# Boost.net
KiCad netlist of a schematic drawn in EAGLE
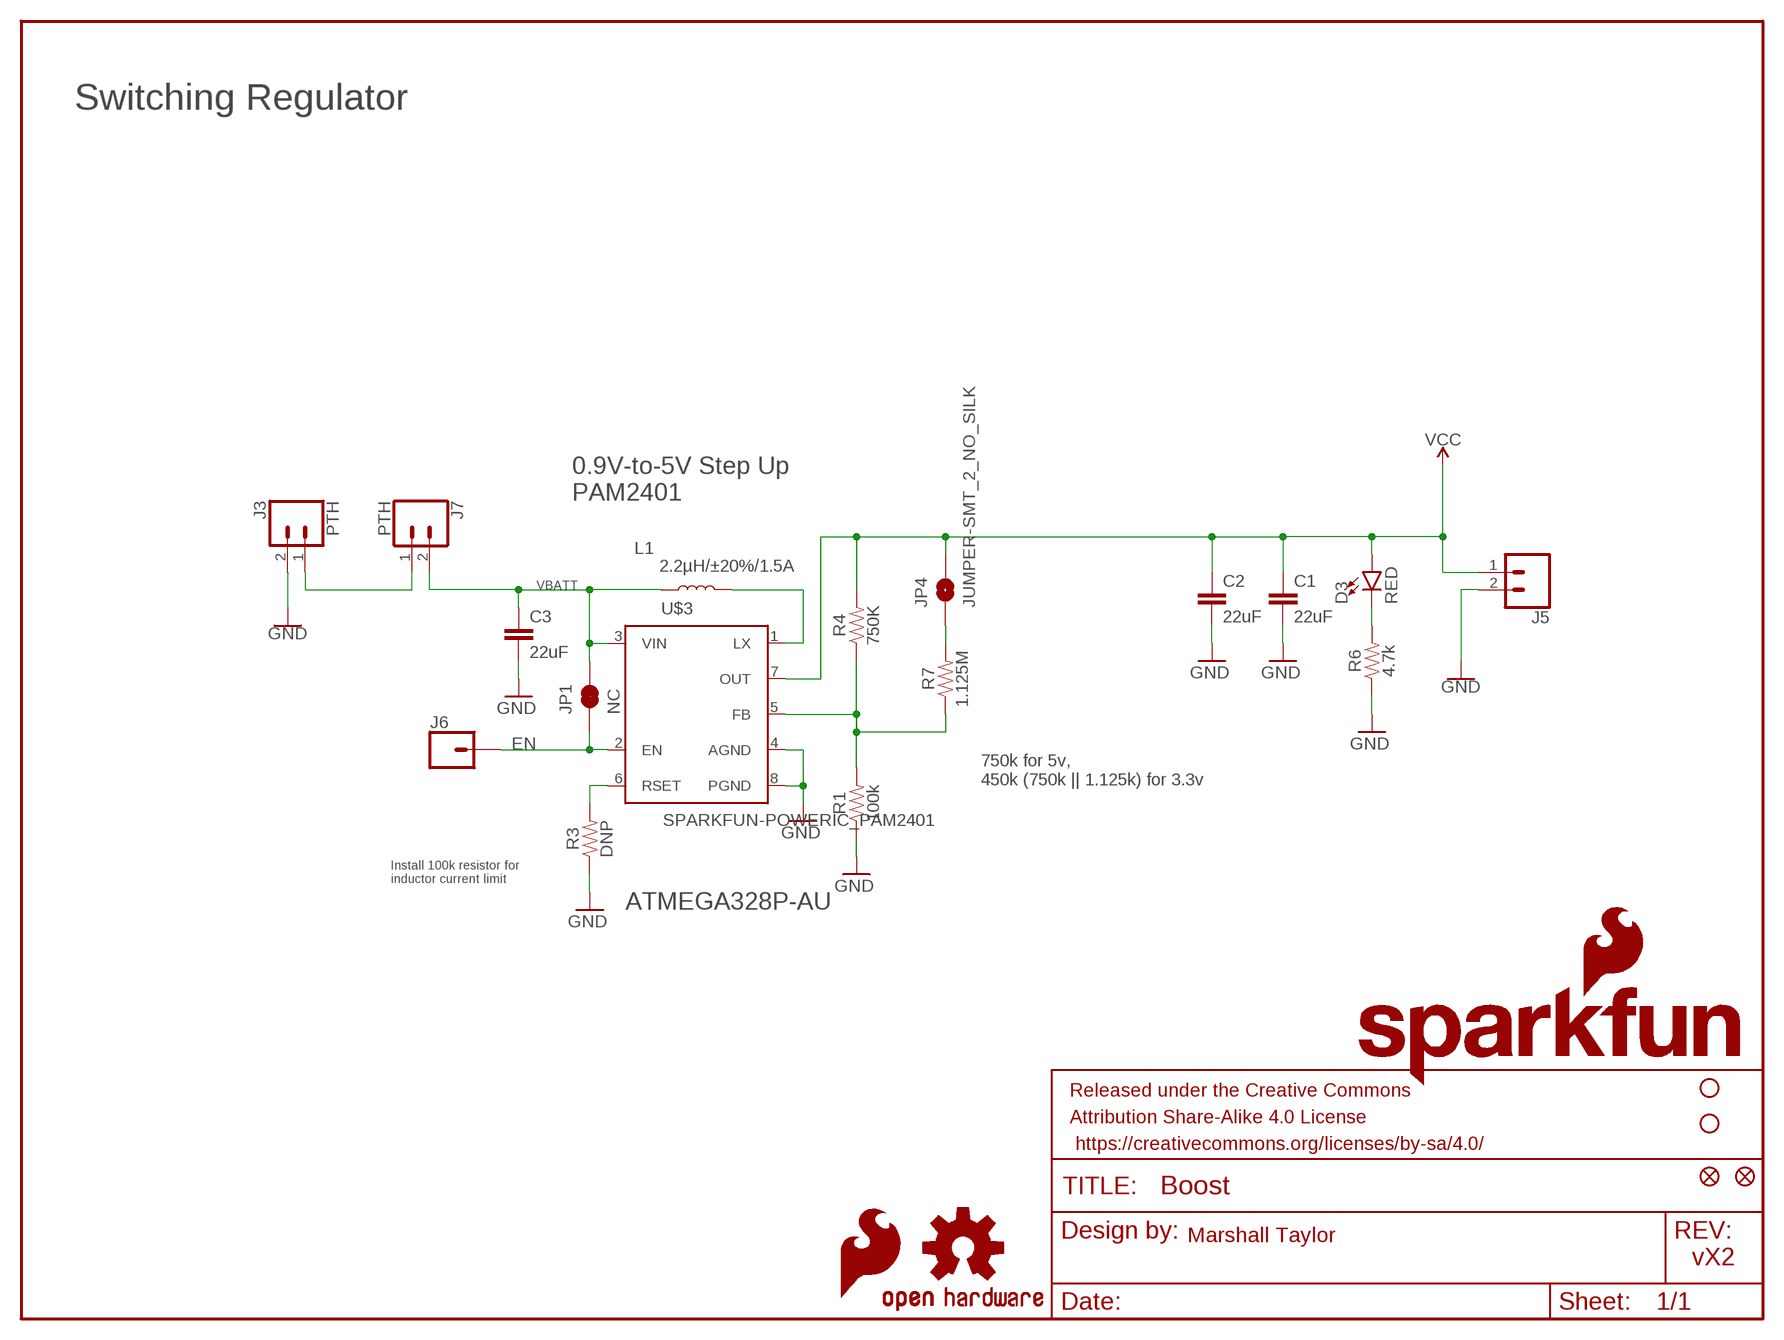
[diagram p0: schematic, sheet 1]

(export (version "E")
  (design (tool "Eeschema 10.0.6"))
  (components
    (comp (ref "C1")
      (value "22uF")
      (footprint "eagle-import:0805")
      (libsource (lib "eagle-import") (part "22UF-0805-6.3V-20%"))
    )
    (comp (ref "C2")
      (value "22uF")
      (footprint "eagle-import:0805")
      (libsource (lib "eagle-import") (part "22UF-0805-6.3V-20%"))
    )
    (comp (ref "C3")
      (value "22uF")
      (footprint "eagle-import:0805")
      (libsource (lib "eagle-import") (part "22UF-0805-6.3V-20%"))
    )
    (comp (ref "D3")
      (value "RED")
      (footprint "eagle-import:LED-0603")
      (libsource (lib "eagle-import") (part "LED-RED0603"))
    )
    (comp (ref "FRAME1")
      (value "FRAME-LETTER")
      (footprint "eagle-import:CREATIVE_COMMONS")
      (libsource (lib "eagle-import") (part "FRAME-LETTER"))
    )
    (comp (ref "J3")
      (value "PTH")
      (footprint "eagle-import:1X02_NO_SILK")
      (libsource (lib "eagle-import") (part "CONN_021X02_NO_SILK"))
    )
    (comp (ref "J5")
      (value "CONN_021X02_NO_SILK")
      (footprint "eagle-import:1X02_NO_SILK")
      (libsource (lib "eagle-import") (part "CONN_021X02_NO_SILK"))
    )
    (comp (ref "J6")
      (value "CONN_01")
      (footprint "eagle-import:1X01")
      (libsource (lib "eagle-import") (part "CONN_01"))
    )
    (comp (ref "J7")
      (value "PTH")
      (footprint "eagle-import:1X02_NO_SILK")
      (libsource (lib "eagle-import") (part "CONN_021X02_NO_SILK"))
    )
    (comp (ref "JP1")
      (value "NC")
      (footprint "eagle-import:SMT-JUMPER_2_NC_TRACE_NO-SILK")
      (libsource (lib "eagle-import") (part "JUMPER-SMT_2_NC_TRACE_NO-SILK"))
    )
    (comp (ref "JP2")
      (value "FIDUCIAL1X2")
      (footprint "eagle-import:FIDUCIAL-1X2")
      (libsource (lib "eagle-import") (part "FIDUCIAL1X2"))
    )
    (comp (ref "JP3")
      (value "SFE_LOGO_NAME_FLAME.1_INCH")
      (footprint "eagle-import:SFE_LOGO_NAME_FLAME_.1")
      (libsource (lib "eagle-import") (part "SFE_LOGO_NAME_FLAME.1_INCH"))
    )
    (comp (ref "JP4")
      (value "JUMPER-SMT_2_NO_SILK")
      (footprint "eagle-import:SMT-JUMPER_2_NO_SILK")
      (libsource (lib "eagle-import") (part "JUMPER-SMT_2_NO_SILK"))
    )
    (comp (ref "JP6")
      (value "STAND-OFF")
      (footprint "eagle-import:STAND-OFF")
      (libsource (lib "eagle-import") (part "STAND-OFF"))
    )
    (comp (ref "JP7")
      (value "STAND-OFF")
      (footprint "eagle-import:STAND-OFF")
      (libsource (lib "eagle-import") (part "STAND-OFF"))
    )
    (comp (ref "JP16")
      (value "FIDUCIAL1X2")
      (footprint "eagle-import:FIDUCIAL-1X2")
      (libsource (lib "eagle-import") (part "FIDUCIAL1X2"))
    )
    (comp (ref "L1")
      (value "2.2µH/±20%/1.5A")
      (footprint "eagle-import:INDUCTOR_2.2UHCOPY")
      (libsource (lib "eagle-import") (part "INDUCTORCOPY-VLF4012AT-2.2UH"))
    )
    (comp (ref "LOGO1")
      (value "SFE_LOGO_FLAME.1_INCH")
      (footprint "eagle-import:SFE_LOGO_FLAME_.1")
      (libsource (lib "eagle-import") (part "SFE_LOGO_FLAME.1_INCH"))
    )
    (comp (ref "R1")
      (value "100k")
      (footprint "eagle-import:0603")
      (libsource (lib "eagle-import") (part "100KOHM-0603-1/10W-1%"))
    )
    (comp (ref "R3")
      (value "DNP")
      (footprint "eagle-import:0603")
      (libsource (lib "eagle-import") (part "100KOHM-0603-1/10W-1%"))
    )
    (comp (ref "R4")
      (value "750K")
      (footprint "eagle-import:0603")
      (libsource (lib "eagle-import") (part "750OHM-0603-1/10W-1%"))
    )
    (comp (ref "R6")
      (value "4.7k")
      (footprint "eagle-import:0603")
      (libsource (lib "eagle-import") (part "4.7KOHM-0603-1/10W-1%"))
    )
    (comp (ref "R7")
      (value "1.125M")
      (footprint "eagle-import:0603")
      (libsource (lib "eagle-import") (part "750OHM-0603-1/10W-1%"))
    )
    (comp (ref "U$1")
      (value "OSHW-LOGOS")
      (footprint "eagle-import:OSHW-LOGO-S")
      (libsource (lib "eagle-import") (part "OSHW-LOGOS"))
    )
    (comp (ref "U$3")
      (value "SPARKFUN-POWERIC_PAM2401")
      (footprint "eagle-import:SPARKFUN-POWERIC_MSOP8")
      (libsource (lib "eagle-import") (part "SPARKFUN-POWERIC_PAM2401"))
    )
  )
  (nets
    (net (code "1") (name "/EN") (class "Default")
      (node (ref "J6") (pin "1") (pinfunction "1_1") (pintype "passive"))
      (node (ref "JP1") (pin "1") (pinfunction "1_1") (pintype "passive"))
      (node (ref "U$3") (pin "2") (pinfunction "EN_2") (pintype "bidirectional"))
    )
    (net (code "2") (name "/VBATT") (class "Default")
      (node (ref "C3") (pin "1") (pinfunction "1_1") (pintype "passive"))
      (node (ref "J7") (pin "2") (pinfunction "2_2") (pintype "passive"))
      (node (ref "JP1") (pin "2") (pinfunction "2_2") (pintype "passive"))
      (node (ref "L1") (pin "P$1") (pinfunction "1_P$1") (pintype "passive"))
      (node (ref "U$3") (pin "3") (pinfunction "VIN_3") (pintype "bidirectional"))
    )
    (net (code "3") (name "GND") (class "Default")
      (node (ref "C1") (pin "2") (pinfunction "2_2") (pintype "passive"))
      (node (ref "C2") (pin "2") (pinfunction "2_2") (pintype "passive"))
      (node (ref "C3") (pin "2") (pinfunction "2_2") (pintype "passive"))
      (node (ref "J3") (pin "2") (pinfunction "2_2") (pintype "passive"))
      (node (ref "J5") (pin "2") (pinfunction "2_2") (pintype "passive"))
      (node (ref "R1") (pin "1") (pinfunction "1_1") (pintype "passive"))
      (node (ref "R3") (pin "1") (pinfunction "1_1") (pintype "passive"))
      (node (ref "R6") (pin "1") (pinfunction "1_1") (pintype "passive"))
      (node (ref "U$3") (pin "4") (pinfunction "AGND_4") (pintype "bidirectional"))
      (node (ref "U$3") (pin "8") (pinfunction "PGND_8") (pintype "bidirectional"))
    )
    (net (code "4") (name "Net-(D3-PadC)") (class "Default")
      (node (ref "D3") (pin "C") (pinfunction "C_C") (pintype "passive"))
      (node (ref "R6") (pin "2") (pinfunction "2_2") (pintype "passive"))
    )
    (net (code "5") (name "Net-(J3-Pad1)") (class "Default")
      (node (ref "J3") (pin "1") (pinfunction "1_1") (pintype "passive"))
      (node (ref "J7") (pin "1") (pinfunction "1_1") (pintype "passive"))
    )
    (net (code "6") (name "Net-(JP4-Pad1)") (class "Default")
      (node (ref "JP4") (pin "1") (pinfunction "1_1") (pintype "passive"))
      (node (ref "R7") (pin "2") (pinfunction "2_2") (pintype "passive"))
    )
    (net (code "7") (name "Net-(L1-2)") (class "Default")
      (node (ref "L1") (pin "P$2") (pinfunction "2_P$2") (pintype "passive"))
      (node (ref "U$3") (pin "1") (pinfunction "LX_1") (pintype "bidirectional"))
    )
    (net (code "8") (name "Net-(U$3-FB)") (class "Default")
      (node (ref "R1") (pin "2") (pinfunction "2_2") (pintype "passive"))
      (node (ref "R4") (pin "1") (pinfunction "1_1") (pintype "passive"))
      (node (ref "R7") (pin "1") (pinfunction "1_1") (pintype "passive"))
      (node (ref "U$3") (pin "5") (pinfunction "FB_5") (pintype "bidirectional"))
    )
    (net (code "9") (name "Net-(U$3-RSET)") (class "Default")
      (node (ref "R3") (pin "2") (pinfunction "2_2") (pintype "passive"))
      (node (ref "U$3") (pin "6") (pinfunction "RSET_6") (pintype "bidirectional"))
    )
    (net (code "10") (name "VCC") (class "Default")
      (node (ref "C1") (pin "1") (pinfunction "1_1") (pintype "passive"))
      (node (ref "C2") (pin "1") (pinfunction "1_1") (pintype "passive"))
      (node (ref "D3") (pin "A") (pinfunction "A_A") (pintype "passive"))
      (node (ref "J5") (pin "1") (pinfunction "1_1") (pintype "passive"))
      (node (ref "JP4") (pin "2") (pinfunction "2_2") (pintype "passive"))
      (node (ref "R4") (pin "2") (pinfunction "2_2") (pintype "passive"))
      (node (ref "U$3") (pin "7") (pinfunction "OUT_7") (pintype "bidirectional"))
    )
  )
)
